# 02-8A34004_DPLL-1.net
KiCad netlist of a schematic drawn in Altium Designer
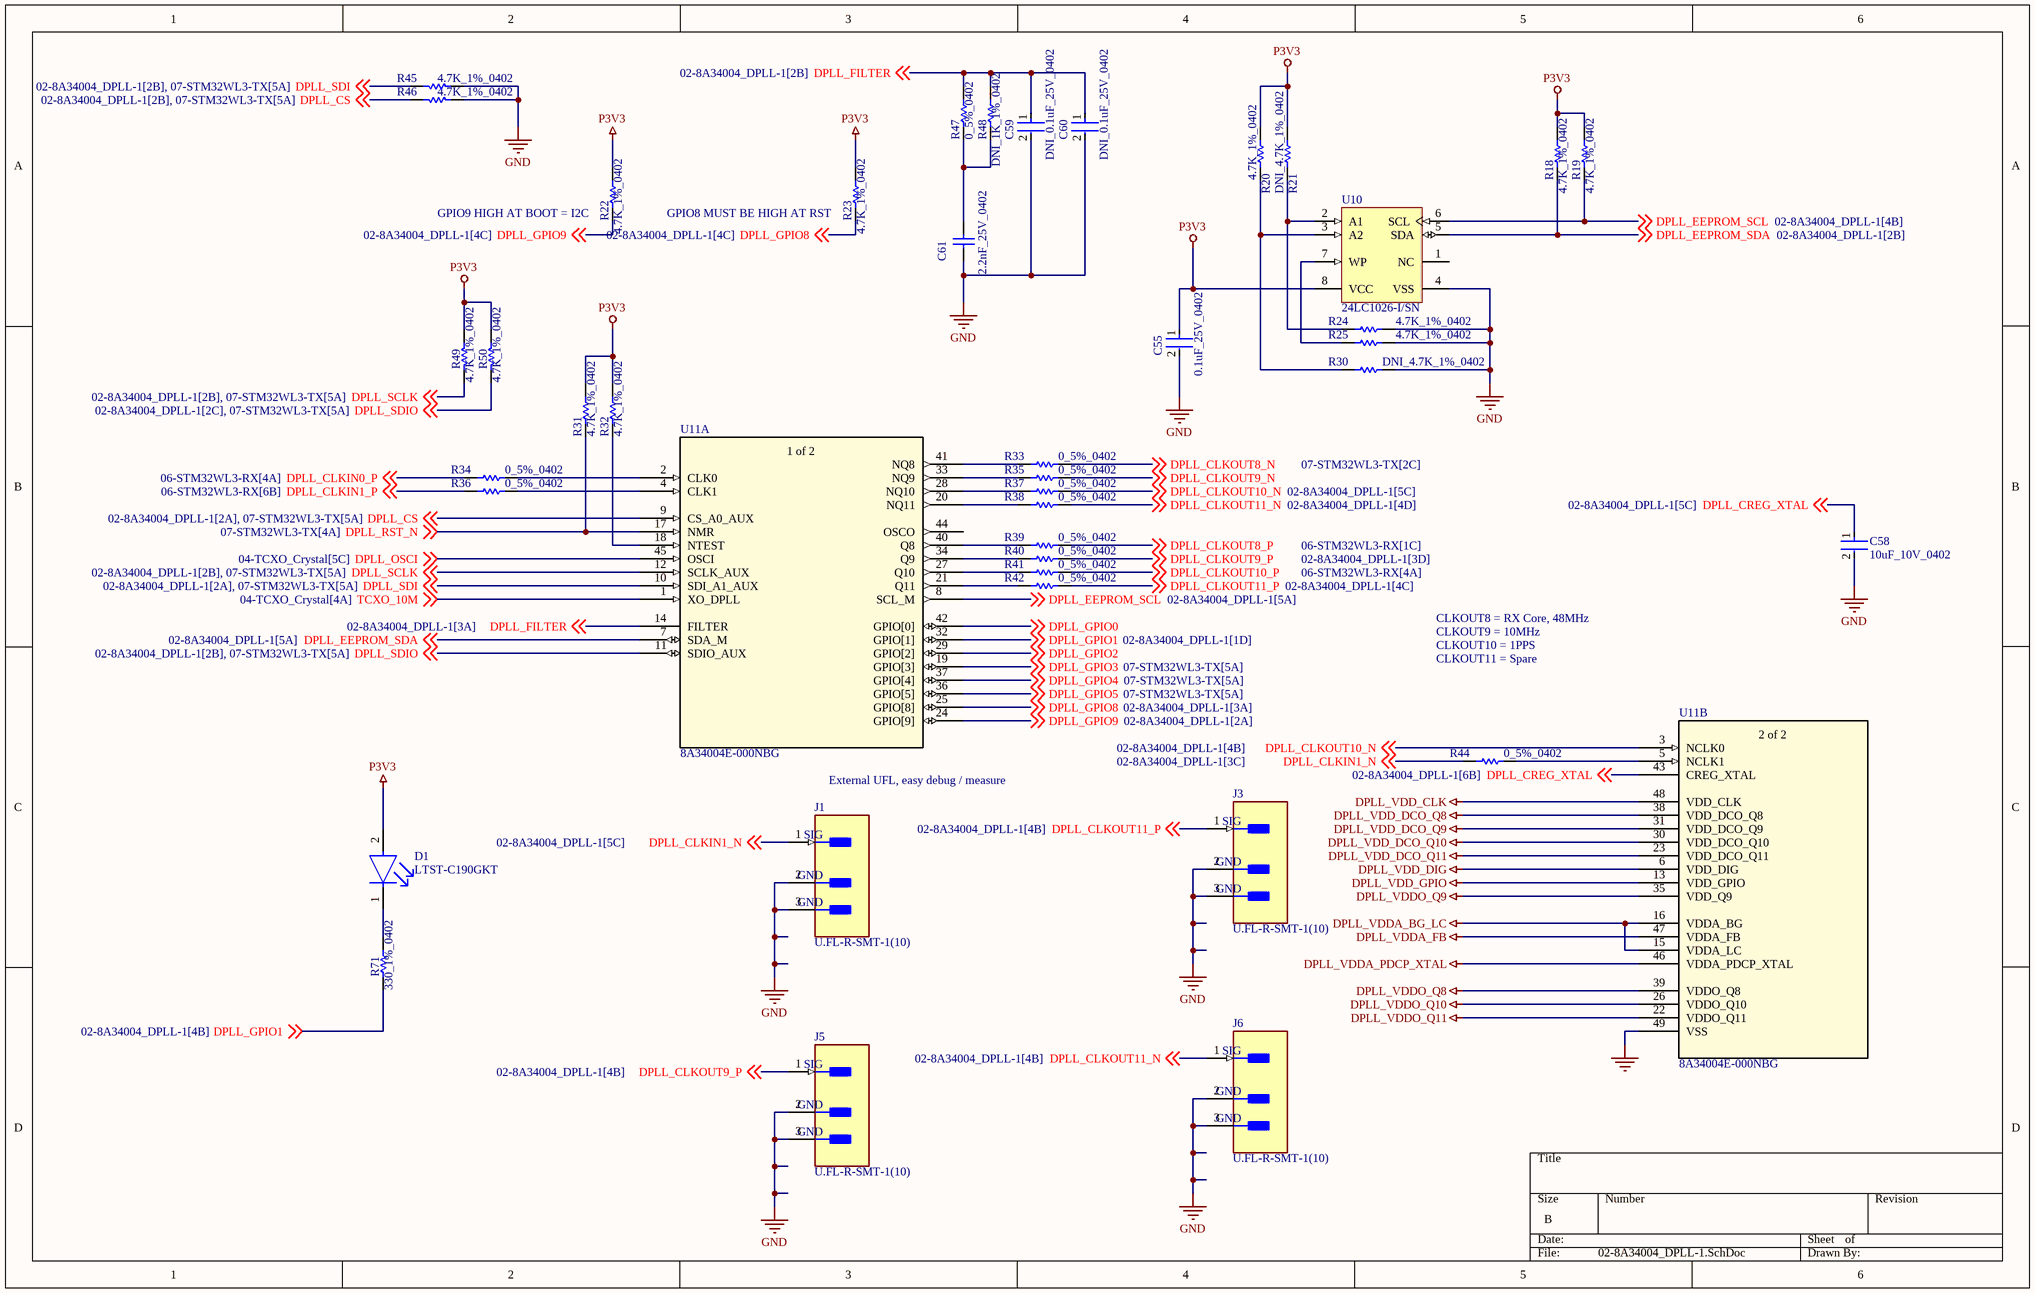
[diagram p0: 02-8A34004_DPLL-1.SchDoc]

(export (version "E")
  (design (tool "Eeschema 10.0.6"))
  (components
    (comp (ref "C55")
      (value "0.1uF_25V_0402")
      (footprint "FP-0402-L_1_0_1-W_0_5_0_1-IPC_C")
      (description "General Purpose Ceramic Capacitor, 0402, 100nF, 10%, X7R, 15%, 25V")
      (fields (field (name "VOLTAGE") "25V") (field (name "TOLERANCE") "10%"))
      (libsource (lib "Altium Content Vault") (part "b4654b650e69147ec39a6b967a45e02"))
    )
    (comp (ref "C58")
      (value "10uF_10V_0402")
      (footprint "FP-CL05A106MP5NUNC-MFG")
      (description "CAP CER 10UF 10V X5R 0402")
      (fields
        (field (name "OCTOPART") "https://octopart.com/cl05a106mp5nunc-samsung-22457395")
        (field (name "TOLERANCE") "20%")
      )
      (libsource (lib "Altium Content Vault") (part "b4654b650e69147ec39a6b967a45e02"))
    )
    (comp (ref "C59")
      (value "DNI_0.1uF_25V_0402")
      (footprint "FP-0402-L_1_0_1-W_0_5_0_1-IPC_C")
      (description "General Purpose Ceramic Capacitor, 0402, 100nF, 10%, X7R, 15%, 25V")
      (fields (field (name "VOLTAGE") "25V") (field (name "TOLERANCE") "10%"))
      (libsource (lib "Altium Content Vault") (part "b4654b650e69147ec39a6b967a45e02"))
    )
    (comp (ref "C60")
      (value "DNI_0.1uF_25V_0402")
      (footprint "FP-0402-L_1_0_1-W_0_5_0_1-IPC_C")
      (description "General Purpose Ceramic Capacitor, 0402, 100nF, 10%, X7R, 15%, 25V")
      (fields (field (name "VOLTAGE") "25V") (field (name "TOLERANCE") "10%"))
      (libsource (lib "Altium Content Vault") (part "b4654b650e69147ec39a6b967a45e02"))
    )
    (comp (ref "C61")
      (value "2.2nF_25V_0402")
      (footprint "CAPC1005X56X25LL10T15")
      (fields
        (field (name "MANUFACTURER") "AVX Interconnect / Elco")
        (field (name "PART NUMBER") "04025C222JAT2A")
      )
      (libsource (lib "Altium Content Vault") (part "CAP"))
    )
    (comp (ref "D1")
      (value "LTST-C190GKT")
      (footprint "FP-LTST-C190GKT-MFG")
      (description "LED GREEN CLEAR CHIP SMD")
      (fields (field (name "VOLTAGE") "2V"))
      (libsource (lib "Altium Content Vault") (part "8706943c75ba83719d021d2fdc84c58"))
    )
    (comp (ref "J1")
      (value "U.FL-R-SMT-1(10)")
      (footprint "FP-U_FL-R-SMT-1_10-MFG")
      (description "CONN U.FL RCPT STR 50 OHM SMD")
      (libsource (lib "Altium Content Vault") (part "7158abf7d987fa84906f6fb0d115710"))
    )
    (comp (ref "J3")
      (value "U.FL-R-SMT-1(10)")
      (footprint "FP-U_FL-R-SMT-1_10-MFG")
      (description "CONN U.FL RCPT STR 50 OHM SMD")
      (libsource (lib "Altium Content Vault") (part "7158abf7d987fa84906f6fb0d115710"))
    )
    (comp (ref "J5")
      (value "U.FL-R-SMT-1(10)")
      (footprint "FP-U_FL-R-SMT-1_10-MFG")
      (description "CONN U.FL RCPT STR 50 OHM SMD")
      (libsource (lib "Altium Content Vault") (part "7158abf7d987fa84906f6fb0d115710"))
    )
    (comp (ref "J6")
      (value "U.FL-R-SMT-1(10)")
      (footprint "FP-U_FL-R-SMT-1_10-MFG")
      (description "CONN U.FL RCPT STR 50 OHM SMD")
      (libsource (lib "Altium Content Vault") (part "7158abf7d987fa84906f6fb0d115710"))
    )
    (comp (ref "R18")
      (value "4.7K_1%_0402")
      (footprint "RESC1005X40X25NL10T10")
      (fields (field (name "MANUFACTURER") "Bourns") (field (name "PART NUMBER") "CR0402-FX-4701GLF"))
      (libsource (lib "Altium Content Vault") (part "RES"))
    )
    (comp (ref "R19")
      (value "4.7K_1%_0402")
      (footprint "RESC1005X40X25NL10T10")
      (fields (field (name "MANUFACTURER") "Bourns") (field (name "PART NUMBER") "CR0402-FX-4701GLF"))
      (libsource (lib "Altium Content Vault") (part "RES"))
    )
    (comp (ref "R20")
      (value "4.7K_1%_0402")
      (footprint "RESC1005X40X25NL10T10")
      (fields (field (name "MANUFACTURER") "Bourns") (field (name "PART NUMBER") "CR0402-FX-4701GLF"))
      (libsource (lib "Altium Content Vault") (part "RES"))
    )
    (comp (ref "R21")
      (value "DNI_4.7K_1%_0402")
      (footprint "RESC1005X40X25NL10T10")
      (fields (field (name "MANUFACTURER") "Bourns") (field (name "PART NUMBER") "CR0402-FX-4701GLF"))
      (libsource (lib "Altium Content Vault") (part "RES"))
    )
    (comp (ref "R22")
      (value "4.7K_1%_0402")
      (footprint "RESC1005X40X25NL10T10")
      (fields (field (name "MANUFACTURER") "Bourns") (field (name "PART NUMBER") "CR0402-FX-4701GLF"))
      (libsource (lib "Altium Content Vault") (part "RES"))
    )
    (comp (ref "R23")
      (value "4.7K_1%_0402")
      (footprint "RESC1005X40X25NL10T10")
      (fields (field (name "MANUFACTURER") "Bourns") (field (name "PART NUMBER") "CR0402-FX-4701GLF"))
      (libsource (lib "Altium Content Vault") (part "RES"))
    )
    (comp (ref "R24")
      (value "4.7K_1%_0402")
      (footprint "RESC1005X40X25NL10T10")
      (fields (field (name "MANUFACTURER") "Bourns") (field (name "PART NUMBER") "CR0402-FX-4701GLF"))
      (libsource (lib "Altium Content Vault") (part "RES"))
    )
    (comp (ref "R25")
      (value "4.7K_1%_0402")
      (footprint "RESC1005X40X25NL10T10")
      (fields (field (name "MANUFACTURER") "Bourns") (field (name "PART NUMBER") "CR0402-FX-4701GLF"))
      (libsource (lib "Altium Content Vault") (part "RES"))
    )
    (comp (ref "R30")
      (value "DNI_4.7K_1%_0402")
      (footprint "RESC1005X40X25NL10T10")
      (fields (field (name "MANUFACTURER") "Bourns") (field (name "PART NUMBER") "CR0402-FX-4701GLF"))
      (libsource (lib "Altium Content Vault") (part "RES"))
    )
    (comp (ref "R31")
      (value "4.7K_1%_0402")
      (footprint "RESC1005X40X25NL10T10")
      (fields (field (name "MANUFACTURER") "Bourns") (field (name "PART NUMBER") "CR0402-FX-4701GLF"))
      (libsource (lib "Altium Content Vault") (part "RES"))
    )
    (comp (ref "R32")
      (value "4.7K_1%_0402")
      (footprint "RESC1005X40X25NL10T10")
      (fields (field (name "MANUFACTURER") "Bourns") (field (name "PART NUMBER") "CR0402-FX-4701GLF"))
      (libsource (lib "Altium Content Vault") (part "RES"))
    )
    (comp (ref "R33")
      (value "0_5%_0402")
      (footprint "RESC1005X40X25NL05T10")
      (fields (field (name "MANUFACTURER") "Panasonic") (field (name "PART NUMBER") "ERJ-U020R00X"))
      (libsource (lib "Altium Content Vault") (part "RES"))
    )
    (comp (ref "R34")
      (value "0_5%_0402")
      (footprint "RESC1005X40X25NL05T10")
      (fields (field (name "MANUFACTURER") "Panasonic") (field (name "PART NUMBER") "ERJ-U020R00X"))
      (libsource (lib "Altium Content Vault") (part "RES"))
    )
    (comp (ref "R35")
      (value "0_5%_0402")
      (footprint "RESC1005X40X25NL05T10")
      (fields (field (name "MANUFACTURER") "Panasonic") (field (name "PART NUMBER") "ERJ-U020R00X"))
      (libsource (lib "Altium Content Vault") (part "RES"))
    )
    (comp (ref "R36")
      (value "0_5%_0402")
      (footprint "RESC1005X40X25NL05T10")
      (fields (field (name "MANUFACTURER") "Panasonic") (field (name "PART NUMBER") "ERJ-U020R00X"))
      (libsource (lib "Altium Content Vault") (part "RES"))
    )
    (comp (ref "R37")
      (value "0_5%_0402")
      (footprint "RESC1005X40X25NL05T10")
      (fields (field (name "MANUFACTURER") "Panasonic") (field (name "PART NUMBER") "ERJ-U020R00X"))
      (libsource (lib "Altium Content Vault") (part "RES"))
    )
    (comp (ref "R38")
      (value "0_5%_0402")
      (footprint "RESC1005X40X25NL05T10")
      (fields (field (name "MANUFACTURER") "Panasonic") (field (name "PART NUMBER") "ERJ-U020R00X"))
      (libsource (lib "Altium Content Vault") (part "RES"))
    )
    (comp (ref "R39")
      (value "0_5%_0402")
      (footprint "RESC1005X40X25NL05T10")
      (fields (field (name "MANUFACTURER") "Panasonic") (field (name "PART NUMBER") "ERJ-U020R00X"))
      (libsource (lib "Altium Content Vault") (part "RES"))
    )
    (comp (ref "R40")
      (value "0_5%_0402")
      (footprint "RESC1005X40X25NL05T10")
      (fields (field (name "MANUFACTURER") "Panasonic") (field (name "PART NUMBER") "ERJ-U020R00X"))
      (libsource (lib "Altium Content Vault") (part "RES"))
    )
    (comp (ref "R41")
      (value "0_5%_0402")
      (footprint "RESC1005X40X25NL05T10")
      (fields (field (name "MANUFACTURER") "Panasonic") (field (name "PART NUMBER") "ERJ-U020R00X"))
      (libsource (lib "Altium Content Vault") (part "RES"))
    )
    (comp (ref "R42")
      (value "0_5%_0402")
      (footprint "RESC1005X40X25NL05T10")
      (fields (field (name "MANUFACTURER") "Panasonic") (field (name "PART NUMBER") "ERJ-U020R00X"))
      (libsource (lib "Altium Content Vault") (part "RES"))
    )
    (comp (ref "R44")
      (value "0_5%_0402")
      (footprint "RESC1005X40X25NL05T10")
      (fields (field (name "MANUFACTURER") "Panasonic") (field (name "PART NUMBER") "ERJ-U020R00X"))
      (libsource (lib "Altium Content Vault") (part "RES"))
    )
    (comp (ref "R45")
      (value "4.7K_1%_0402")
      (footprint "RESC1005X40X25NL10T10")
      (fields (field (name "MANUFACTURER") "Bourns") (field (name "PART NUMBER") "CR0402-FX-4701GLF"))
      (libsource (lib "Altium Content Vault") (part "RES"))
    )
    (comp (ref "R46")
      (value "4.7K_1%_0402")
      (footprint "RESC1005X40X25NL10T10")
      (fields (field (name "MANUFACTURER") "Bourns") (field (name "PART NUMBER") "CR0402-FX-4701GLF"))
      (libsource (lib "Altium Content Vault") (part "RES"))
    )
    (comp (ref "R47")
      (value "0_5%_0402")
      (footprint "RESC1005X40X25LL10T10")
      (fields (field (name "MANUFACTURER") "KOA Speer") (field (name "PART NUMBER") "RK73Z1ETTP"))
      (libsource (lib "Altium Content Vault") (part "RES"))
    )
    (comp (ref "R48")
      (value "DNI_1K_1%_0402")
      (footprint "RESC1005X40X25NL05T05")
      (fields (field (name "MANUFACTURER") "Vishay Dale") (field (name "PART NUMBER") "CRCW04021K00FKTD"))
      (libsource (lib "Altium Content Vault") (part "RES"))
    )
    (comp (ref "R49")
      (value "4.7K_1%_0402")
      (footprint "RESC1005X40X25NL10T10")
      (fields (field (name "MANUFACTURER") "Bourns") (field (name "PART NUMBER") "CR0402-FX-4701GLF"))
      (libsource (lib "Altium Content Vault") (part "RES"))
    )
    (comp (ref "R50")
      (value "4.7K_1%_0402")
      (footprint "RESC1005X40X25NL10T10")
      (fields (field (name "MANUFACTURER") "Bourns") (field (name "PART NUMBER") "CR0402-FX-4701GLF"))
      (libsource (lib "Altium Content Vault") (part "RES"))
    )
    (comp (ref "R71")
      (value "330_1%_0402")
      (footprint "RESC1005X40X25NL10T10")
      (fields (field (name "MANUFACTURER") "Panasonic") (field (name "PART NUMBER") "ERA-2AED331X"))
      (libsource (lib "Altium Content Vault") (part "RES"))
    )
    (comp (ref "U10")
      (value "24LC1026-I/SN")
      (footprint "MCHP-SOIC-SN8_N")
      (description "1024K bits I2C™ Serial EEPROM, 2.5 to 5.5 V, 400 kHz, -40 to 85 degC, 8-pin SOIC (SN8), Tube")
      (fields (field (name "MANUFACTURER") "Microchip"))
      (libsource (lib "Altium Content Vault") (part "MCHP-24LC1026-SOIC-8"))
    )
    (comp (ref "U11")
      (value "8A34004E-000NBG")
      (footprint "NBG48P1_REN")
      (description "No Description Available")
      (libsource (lib "8A34004E-000NBG") (part "8A34004E-000NBG"))
    )
  )
  (nets
    (net (code "1") (name "DPLL_CLKIN0_P") (class "Default")
      (node (ref "R34") (pin "1") (pinfunction "1_1") (pintype "passive"))
    )
    (net (code "2") (name "DPLL_CLKIN1_N") (class "Default")
      (node (ref "J1") (pin "1") (pinfunction "SIG_1") (pintype "input"))
      (node (ref "R44") (pin "1") (pinfunction "1_1") (pintype "passive"))
    )
    (net (code "3") (name "DPLL_CLKIN1_P") (class "Default")
      (node (ref "R36") (pin "1") (pinfunction "1_1") (pintype "passive"))
    )
    (net (code "4") (name "DPLL_CLKOUT8_N") (class "Default")
      (node (ref "R33") (pin "2") (pinfunction "2_2") (pintype "passive"))
    )
    (net (code "5") (name "DPLL_CLKOUT8_P") (class "Default")
      (node (ref "R39") (pin "2") (pinfunction "2_2") (pintype "passive"))
    )
    (net (code "6") (name "DPLL_CLKOUT9_N") (class "Default")
      (node (ref "R35") (pin "2") (pinfunction "2_2") (pintype "passive"))
    )
    (net (code "7") (name "DPLL_CLKOUT9_P") (class "Default")
      (node (ref "J5") (pin "1") (pinfunction "SIG_1") (pintype "input"))
      (node (ref "R40") (pin "2") (pinfunction "2_2") (pintype "passive"))
    )
    (net (code "8") (name "DPLL_CLKOUT10_N") (class "Default")
      (node (ref "R37") (pin "2") (pinfunction "2_2") (pintype "passive"))
      (node (ref "U11") (pin "3") (pinfunction "NCLK0_3") (pintype "input"))
    )
    (net (code "9") (name "DPLL_CLKOUT10_P") (class "Default")
      (node (ref "R41") (pin "2") (pinfunction "2_2") (pintype "passive"))
    )
    (net (code "10") (name "DPLL_CLKOUT11_N") (class "Default")
      (node (ref "J6") (pin "1") (pinfunction "SIG_1") (pintype "input"))
      (node (ref "R38") (pin "2") (pinfunction "2_2") (pintype "passive"))
    )
    (net (code "11") (name "DPLL_CLKOUT11_P") (class "Default")
      (node (ref "J3") (pin "1") (pinfunction "SIG_1") (pintype "input"))
      (node (ref "R42") (pin "2") (pinfunction "2_2") (pintype "passive"))
    )
    (net (code "12") (name "DPLL_CREG_XTAL") (class "Default")
      (node (ref "C58") (pin "1") (pinfunction "1_1") (pintype "passive"))
      (node (ref "U11") (pin "43") (pinfunction "CREG_XTAL_43") (pintype "power_in"))
    )
    (net (code "13") (name "DPLL_CS") (class "Default")
      (node (ref "R46") (pin "1") (pinfunction "1_1") (pintype "passive"))
      (node (ref "U11") (pin "9") (pinfunction "CS_A0_AUX_9") (pintype "input"))
    )
    (net (code "14") (name "DPLL_EEPROM_SCL") (class "Default")
      (node (ref "R19") (pin "2") (pinfunction "2_2") (pintype "passive"))
      (node (ref "U10") (pin "6") (pinfunction "SCL_6") (pintype "input"))
      (node (ref "U11") (pin "8") (pinfunction "SCL_M_8") (pintype "output"))
    )
    (net (code "15") (name "DPLL_EEPROM_SDA") (class "Default")
      (node (ref "R18") (pin "2") (pinfunction "2_2") (pintype "passive"))
      (node (ref "U10") (pin "5") (pinfunction "SDA_5") (pintype "bidirectional"))
      (node (ref "U11") (pin "7") (pinfunction "SDA_M_7") (pintype "bidirectional"))
    )
    (net (code "16") (name "DPLL_FILTER") (class "Default")
      (node (ref "C59") (pin "1") (pinfunction "1_1") (pintype "passive"))
      (node (ref "C60") (pin "1") (pinfunction "1_1") (pintype "passive"))
      (node (ref "R47") (pin "2") (pinfunction "2_2") (pintype "passive"))
      (node (ref "R48") (pin "2") (pinfunction "2_2") (pintype "passive"))
      (node (ref "U11") (pin "14") (pinfunction "FILTER_14") (pintype "passive"))
    )
    (net (code "17") (name "DPLL_GPIO0") (class "Default")
      (node (ref "U11") (pin "42") (pinfunction "GPIO[0]_42") (pintype "bidirectional"))
    )
    (net (code "18") (name "DPLL_GPIO1") (class "Default")
      (node (ref "R71") (pin "1") (pinfunction "1_1") (pintype "passive"))
      (node (ref "U11") (pin "32") (pinfunction "GPIO[1]_32") (pintype "bidirectional"))
    )
    (net (code "19") (name "DPLL_GPIO2") (class "Default")
      (node (ref "U11") (pin "29") (pinfunction "GPIO[2]_29") (pintype "bidirectional"))
    )
    (net (code "20") (name "DPLL_GPIO3") (class "Default")
      (node (ref "U11") (pin "19") (pinfunction "GPIO[3]_19") (pintype "bidirectional"))
    )
    (net (code "21") (name "DPLL_GPIO4") (class "Default")
      (node (ref "U11") (pin "37") (pinfunction "GPIO[4]_37") (pintype "bidirectional"))
    )
    (net (code "22") (name "DPLL_GPIO5") (class "Default")
      (node (ref "U11") (pin "36") (pinfunction "GPIO[5]_36") (pintype "bidirectional"))
    )
    (net (code "23") (name "DPLL_GPIO8") (class "Default")
      (node (ref "R23") (pin "2") (pinfunction "2_2") (pintype "passive"))
      (node (ref "U11") (pin "25") (pinfunction "GPIO[8]_25") (pintype "bidirectional"))
    )
    (net (code "24") (name "DPLL_GPIO9") (class "Default")
      (node (ref "R22") (pin "2") (pinfunction "2_2") (pintype "passive"))
      (node (ref "U11") (pin "24") (pinfunction "GPIO[9]_24") (pintype "bidirectional"))
    )
    (net (code "25") (name "DPLL_OSCI") (class "Default")
      (node (ref "U11") (pin "45") (pinfunction "OSCI_45") (pintype "input"))
    )
    (net (code "26") (name "DPLL_RST_N") (class "Default")
      (node (ref "R31") (pin "1") (pinfunction "1_1") (pintype "passive"))
      (node (ref "U11") (pin "17") (pinfunction "NMR_17") (pintype "input"))
    )
    (net (code "27") (name "DPLL_SCLK") (class "Default")
      (node (ref "R49") (pin "1") (pinfunction "1_1") (pintype "passive"))
      (node (ref "U11") (pin "12") (pinfunction "SCLK_AUX_12") (pintype "input"))
    )
    (net (code "28") (name "DPLL_SDI") (class "Default")
      (node (ref "R45") (pin "1") (pinfunction "1_1") (pintype "passive"))
      (node (ref "U11") (pin "10") (pinfunction "SDI_A1_AUX_10") (pintype "input"))
    )
    (net (code "29") (name "DPLL_SDIO") (class "Default")
      (node (ref "R50") (pin "1") (pinfunction "1_1") (pintype "passive"))
      (node (ref "U11") (pin "11") (pinfunction "SDIO_AUX_11") (pintype "bidirectional"))
    )
    (net (code "30") (name "DPLL_VDDA_BG_LC") (class "Default")
      (node (ref "U11") (pin "15") (pinfunction "VDDA_LC_15") (pintype "power_in"))
      (node (ref "U11") (pin "16") (pinfunction "VDDA_BG_16") (pintype "power_in"))
    )
    (net (code "31") (name "DPLL_VDDA_FB") (class "Default")
      (node (ref "U11") (pin "47") (pinfunction "VDDA_FB_47") (pintype "power_in"))
    )
    (net (code "32") (name "DPLL_VDDA_PDCP_XTAL") (class "Default")
      (node (ref "U11") (pin "46") (pinfunction "VDDA_PDCP_XTAL_46") (pintype "power_in"))
    )
    (net (code "33") (name "DPLL_VDDO_Q8") (class "Default")
      (node (ref "U11") (pin "39") (pinfunction "VDDO_Q8_39") (pintype "power_in"))
    )
    (net (code "34") (name "DPLL_VDDO_Q9") (class "Default")
      (node (ref "U11") (pin "35") (pinfunction "VDD_Q9_35") (pintype "power_in"))
    )
    (net (code "35") (name "DPLL_VDDO_Q10") (class "Default")
      (node (ref "U11") (pin "26") (pinfunction "VDDO_Q10_26") (pintype "power_in"))
    )
    (net (code "36") (name "DPLL_VDDO_Q11") (class "Default")
      (node (ref "U11") (pin "22") (pinfunction "VDDO_Q11_22") (pintype "power_in"))
    )
    (net (code "37") (name "DPLL_VDD_CLK") (class "Default")
      (node (ref "U11") (pin "48") (pinfunction "VDD_CLK_48") (pintype "power_in"))
    )
    (net (code "38") (name "DPLL_VDD_DCO_Q8") (class "Default")
      (node (ref "U11") (pin "38") (pinfunction "VDD_DCO_Q8_38") (pintype "power_in"))
    )
    (net (code "39") (name "DPLL_VDD_DCO_Q9") (class "Default")
      (node (ref "U11") (pin "31") (pinfunction "VDD_DCO_Q9_31") (pintype "power_in"))
    )
    (net (code "40") (name "DPLL_VDD_DCO_Q10") (class "Default")
      (node (ref "U11") (pin "30") (pinfunction "VDD_DCO_Q10_30") (pintype "power_in"))
    )
    (net (code "41") (name "DPLL_VDD_DCO_Q11") (class "Default")
      (node (ref "U11") (pin "23") (pinfunction "VDD_DCO_Q11_23") (pintype "power_in"))
    )
    (net (code "42") (name "DPLL_VDD_DIG") (class "Default")
      (node (ref "U11") (pin "6") (pinfunction "VDD_DIG_6") (pintype "power_in"))
    )
    (net (code "43") (name "DPLL_VDD_GPIO") (class "Default")
      (node (ref "U11") (pin "13") (pinfunction "VDD_GPIO_13") (pintype "power_in"))
    )
    (net (code "44") (name "GND") (class "Default")
      (node (ref "C55") (pin "2") (pinfunction "2_2") (pintype "passive"))
      (node (ref "C58") (pin "2") (pinfunction "2_2") (pintype "passive"))
      (node (ref "C59") (pin "2") (pinfunction "2_2") (pintype "passive"))
      (node (ref "C60") (pin "2") (pinfunction "2_2") (pintype "passive"))
      (node (ref "C61") (pin "1") (pinfunction "1_1") (pintype "passive"))
      (node (ref "J1") (pin "2") (pinfunction "GND_2") (pintype "power_in"))
      (node (ref "J1") (pin "3") (pinfunction "GND_3") (pintype "power_in"))
      (node (ref "J3") (pin "2") (pinfunction "GND_2") (pintype "power_in"))
      (node (ref "J3") (pin "3") (pinfunction "GND_3") (pintype "power_in"))
      (node (ref "J5") (pin "2") (pinfunction "GND_2") (pintype "power_in"))
      (node (ref "J5") (pin "3") (pinfunction "GND_3") (pintype "power_in"))
      (node (ref "J6") (pin "2") (pinfunction "GND_2") (pintype "power_in"))
      (node (ref "J6") (pin "3") (pinfunction "GND_3") (pintype "power_in"))
      (node (ref "R24") (pin "1") (pinfunction "1_1") (pintype "passive"))
      (node (ref "R25") (pin "1") (pinfunction "1_1") (pintype "passive"))
      (node (ref "R30") (pin "2") (pinfunction "2_2") (pintype "passive"))
      (node (ref "R45") (pin "2") (pinfunction "2_2") (pintype "passive"))
      (node (ref "R46") (pin "2") (pinfunction "2_2") (pintype "passive"))
      (node (ref "U10") (pin "4") (pinfunction "VSS_4") (pintype "power_in"))
      (node (ref "U11") (pin "49") (pinfunction "VSS_49") (pintype "power_in"))
    )
    (net (code "45") (name "Net-(C61-Pad2)") (class "Default")
      (node (ref "C61") (pin "2") (pinfunction "2_2") (pintype "passive"))
      (node (ref "R47") (pin "1") (pinfunction "1_1") (pintype "passive"))
      (node (ref "R48") (pin "1") (pinfunction "1_1") (pintype "passive"))
    )
    (net (code "46") (name "Net-(D1-C)") (class "Default")
      (node (ref "D1") (pin "1") (pinfunction "C_1") (pintype "passive"))
      (node (ref "R71") (pin "2") (pinfunction "2_2") (pintype "passive"))
    )
    (net (code "47") (name "Net-(U10-A1)") (class "Default")
      (node (ref "R21") (pin "1") (pinfunction "1_1") (pintype "passive"))
      (node (ref "R24") (pin "2") (pinfunction "2_2") (pintype "passive"))
      (node (ref "U10") (pin "2") (pinfunction "A1_2") (pintype "input"))
    )
    (net (code "48") (name "Net-(U10-A2)") (class "Default")
      (node (ref "R20") (pin "1") (pinfunction "1_1") (pintype "passive"))
      (node (ref "R30") (pin "1") (pinfunction "1_1") (pintype "passive"))
      (node (ref "U10") (pin "3") (pinfunction "A2_3") (pintype "input"))
    )
    (net (code "49") (name "Net-(U10-WP)") (class "Default")
      (node (ref "R25") (pin "2") (pinfunction "2_2") (pintype "passive"))
      (node (ref "U10") (pin "7") (pinfunction "WP_7") (pintype "input"))
    )
    (net (code "50") (name "Net-(U11A-CLK0)") (class "Default")
      (node (ref "R34") (pin "2") (pinfunction "2_2") (pintype "passive"))
      (node (ref "U11") (pin "2") (pinfunction "CLK0_2") (pintype "input"))
    )
    (net (code "51") (name "Net-(U11A-CLK1)") (class "Default")
      (node (ref "R36") (pin "2") (pinfunction "2_2") (pintype "passive"))
      (node (ref "U11") (pin "4") (pinfunction "CLK1_4") (pintype "input"))
    )
    (net (code "52") (name "Net-(U11A-NQ8)") (class "Default")
      (node (ref "R33") (pin "1") (pinfunction "1_1") (pintype "passive"))
      (node (ref "U11") (pin "41") (pinfunction "NQ8_41") (pintype "output"))
    )
    (net (code "53") (name "Net-(U11A-NQ9)") (class "Default")
      (node (ref "R35") (pin "1") (pinfunction "1_1") (pintype "passive"))
      (node (ref "U11") (pin "33") (pinfunction "NQ9_33") (pintype "output"))
    )
    (net (code "54") (name "Net-(U11A-NQ10)") (class "Default")
      (node (ref "R37") (pin "1") (pinfunction "1_1") (pintype "passive"))
      (node (ref "U11") (pin "28") (pinfunction "NQ10_28") (pintype "output"))
    )
    (net (code "55") (name "Net-(U11A-NQ11)") (class "Default")
      (node (ref "R38") (pin "1") (pinfunction "1_1") (pintype "passive"))
      (node (ref "U11") (pin "20") (pinfunction "NQ11_20") (pintype "output"))
    )
    (net (code "56") (name "Net-(U11A-NTEST)") (class "Default")
      (node (ref "R32") (pin "1") (pinfunction "1_1") (pintype "passive"))
      (node (ref "U11") (pin "18") (pinfunction "NTEST_18") (pintype "input"))
    )
    (net (code "57") (name "Net-(U11A-Q8)") (class "Default")
      (node (ref "R39") (pin "1") (pinfunction "1_1") (pintype "passive"))
      (node (ref "U11") (pin "40") (pinfunction "Q8_40") (pintype "output"))
    )
    (net (code "58") (name "Net-(U11A-Q9)") (class "Default")
      (node (ref "R40") (pin "1") (pinfunction "1_1") (pintype "passive"))
      (node (ref "U11") (pin "34") (pinfunction "Q9_34") (pintype "output"))
    )
    (net (code "59") (name "Net-(U11A-Q10)") (class "Default")
      (node (ref "R41") (pin "1") (pinfunction "1_1") (pintype "passive"))
      (node (ref "U11") (pin "27") (pinfunction "Q10_27") (pintype "output"))
    )
    (net (code "60") (name "Net-(U11A-Q11)") (class "Default")
      (node (ref "R42") (pin "1") (pinfunction "1_1") (pintype "passive"))
      (node (ref "U11") (pin "21") (pinfunction "Q11_21") (pintype "output"))
    )
    (net (code "61") (name "Net-(U11B-NCLK1)") (class "Default")
      (node (ref "R44") (pin "2") (pinfunction "2_2") (pintype "passive"))
      (node (ref "U11") (pin "5") (pinfunction "NCLK1_5") (pintype "input"))
    )
    (net (code "62") (name "P3V3") (class "Default")
      (node (ref "C55") (pin "1") (pinfunction "1_1") (pintype "passive"))
      (node (ref "D1") (pin "2") (pinfunction "A_2") (pintype "passive"))
      (node (ref "R18") (pin "1") (pinfunction "1_1") (pintype "passive"))
      (node (ref "R19") (pin "1") (pinfunction "1_1") (pintype "passive"))
      (node (ref "R20") (pin "2") (pinfunction "2_2") (pintype "passive"))
      (node (ref "R21") (pin "2") (pinfunction "2_2") (pintype "passive"))
      (node (ref "R22") (pin "1") (pinfunction "1_1") (pintype "passive"))
      (node (ref "R23") (pin "1") (pinfunction "1_1") (pintype "passive"))
      (node (ref "R31") (pin "2") (pinfunction "2_2") (pintype "passive"))
      (node (ref "R32") (pin "2") (pinfunction "2_2") (pintype "passive"))
      (node (ref "R49") (pin "2") (pinfunction "2_2") (pintype "passive"))
      (node (ref "R50") (pin "2") (pinfunction "2_2") (pintype "passive"))
      (node (ref "U10") (pin "8") (pinfunction "VCC_8") (pintype "power_in"))
    )
    (net (code "63") (name "TCXO_10M") (class "Default")
      (node (ref "U11") (pin "1") (pinfunction "XO_DPLL_1") (pintype "input"))
    )
    (net (code "64") (name "unconnected-(U10-NC-Pad1)") (class "Default")
      (node (ref "U10") (pin "1") (pinfunction "NC_1") (pintype "passive"))
    )
    (net (code "65") (name "unconnected-(U11A-OSCO-Pad44)") (class "Default")
      (node (ref "U11") (pin "44") (pinfunction "OSCO_44") (pintype "output"))
    )
  )
)
